# IO.net
KiCad netlist of a schematic drawn in Altium Designer
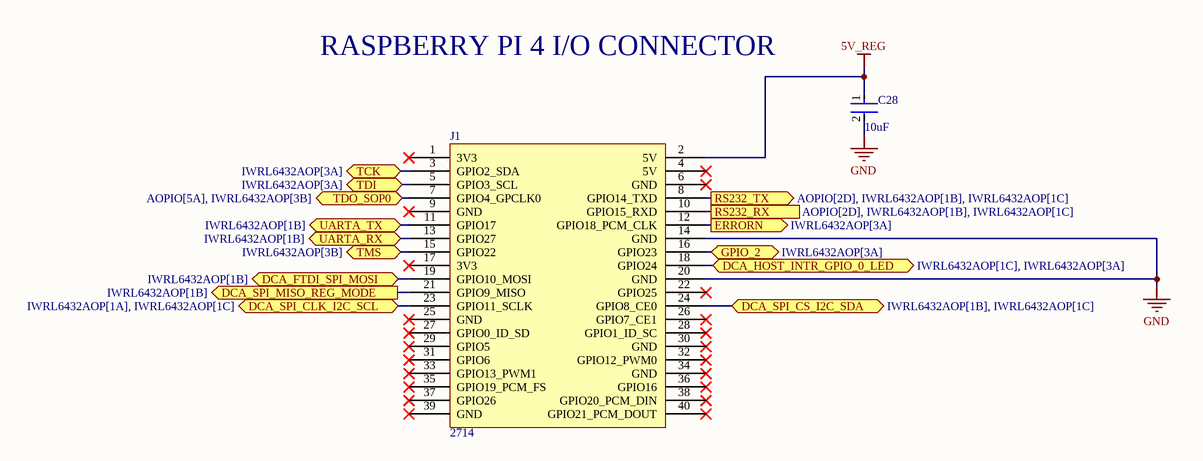
[diagram p0: IO.SchDoc]

(export (version "E")
  (design (tool "Eeschema 10.0.6"))
  (components
    (comp (ref "C28")
      (value "GRM188C81A106MA73D")
      (footprint "FP-GRM188-0_2-MFG")
      (description "Chip Multilayer Ceramic Capacitors for General Purpose, 0603, 10uF, X6S, 22%, 20%, 10V")
      (fields (field (name "TOLERANCE") "20%") (field (name "CAPACITANCE") "10uF"))
      (libsource (lib "Altium Content Vault") (part "11868f565c42a9108669ba33697ecf6"))
    )
    (comp (ref "J1")
      (value "2714")
      (footprint "2714")
      (description "Extra-Tall Smt Gpio Header For Raspberry Pi Hat - 2X20 Extra Tall Female Header ¦Adafruit 2714")
      (fields (field (name "MANUFACTURER") "Adafruit Industries"))
      (libsource (lib "Schlib1") (part "2714"))
    )
  )
  (nets
    (net (code "1") (name "/DCA_FTDI_SPI_MOSI") (class "Default")
      (node (ref "J1") (pin "19") (pinfunction "GPIO10_MOSI_19") (pintype "passive"))
    )
    (net (code "2") (name "/DCA_HOST_INTR_GPIO_0_LED") (class "Default")
      (node (ref "J1") (pin "18") (pinfunction "GPIO24_18") (pintype "passive"))
    )
    (net (code "3") (name "/DCA_SPI_CLK_I2C_SCL") (class "Default")
      (node (ref "J1") (pin "23") (pinfunction "GPIO11_SCLK_23") (pintype "passive"))
    )
    (net (code "4") (name "/DCA_SPI_CS_I2C_SDA") (class "Default")
      (node (ref "J1") (pin "24") (pinfunction "GPIO8_CE0_24") (pintype "passive"))
    )
    (net (code "5") (name "/DCA_SPI_MISO_REG_MODE") (class "Default")
      (node (ref "J1") (pin "21") (pinfunction "GPIO9_MISO_21") (pintype "passive"))
    )
    (net (code "6") (name "/ERRORN") (class "Default")
      (node (ref "J1") (pin "12") (pinfunction "GPIO18_PCM_CLK_12") (pintype "passive"))
    )
    (net (code "7") (name "/GPIO_2") (class "Default")
      (node (ref "J1") (pin "16") (pinfunction "GPIO23_16") (pintype "passive"))
    )
    (net (code "8") (name "/RS232_RX") (class "Default")
      (node (ref "J1") (pin "10") (pinfunction "GPIO15_RXD_10") (pintype "passive"))
    )
    (net (code "9") (name "/RS232_TX") (class "Default")
      (node (ref "J1") (pin "8") (pinfunction "GPIO14_TXD_8") (pintype "passive"))
    )
    (net (code "10") (name "/TCK") (class "Default")
      (node (ref "J1") (pin "3") (pinfunction "GPIO2_SDA_3") (pintype "passive"))
    )
    (net (code "11") (name "/TDI") (class "Default")
      (node (ref "J1") (pin "5") (pinfunction "GPIO3_SCL_5") (pintype "passive"))
    )
    (net (code "12") (name "/TDO_SOP0") (class "Default")
      (node (ref "J1") (pin "7") (pinfunction "GPIO4_GPCLK0_7") (pintype "passive"))
    )
    (net (code "13") (name "/TMS") (class "Default")
      (node (ref "J1") (pin "15") (pinfunction "GPIO22_15") (pintype "passive"))
    )
    (net (code "14") (name "/UARTA_RX") (class "Default")
      (node (ref "J1") (pin "13") (pinfunction "GPIO27_13") (pintype "passive"))
    )
    (net (code "15") (name "/UARTA_TX") (class "Default")
      (node (ref "J1") (pin "11") (pinfunction "GPIO17_11") (pintype "passive"))
    )
    (net (code "16") (name "5V_REG") (class "Default")
      (node (ref "C28") (pin "1") (pinfunction "1_1") (pintype "passive"))
      (node (ref "J1") (pin "2") (pinfunction "5V_2") (pintype "passive"))
    )
    (net (code "17") (name "GND") (class "Default")
      (node (ref "C28") (pin "2") (pinfunction "2_2") (pintype "passive"))
      (node (ref "J1") (pin "14") (pinfunction "GND_14") (pintype "passive"))
      (node (ref "J1") (pin "20") (pinfunction "GND_20") (pintype "passive"))
    )
    (net (code "18") (name "unconnected-(J1-3V3-Pad1)") (class "Default")
      (node (ref "J1") (pin "1") (pinfunction "3V3_1") (pintype "passive+no_connect"))
    )
    (net (code "19") (name "unconnected-(J1-3V3-Pad17)") (class "Default")
      (node (ref "J1") (pin "17") (pinfunction "3V3_17") (pintype "passive+no_connect"))
    )
    (net (code "20") (name "unconnected-(J1-5V-Pad4)") (class "Default")
      (node (ref "J1") (pin "4") (pinfunction "5V_4") (pintype "passive+no_connect"))
    )
    (net (code "21") (name "unconnected-(J1-GND-Pad6)") (class "Default")
      (node (ref "J1") (pin "6") (pinfunction "GND_6") (pintype "passive+no_connect"))
    )
    (net (code "22") (name "unconnected-(J1-GND-Pad9)") (class "Default")
      (node (ref "J1") (pin "9") (pinfunction "GND_9") (pintype "passive+no_connect"))
    )
    (net (code "23") (name "unconnected-(J1-GND-Pad25)") (class "Default")
      (node (ref "J1") (pin "25") (pinfunction "GND_25") (pintype "passive+no_connect"))
    )
    (net (code "24") (name "unconnected-(J1-GND-Pad30)") (class "Default")
      (node (ref "J1") (pin "30") (pinfunction "GND_30") (pintype "passive+no_connect"))
    )
    (net (code "25") (name "unconnected-(J1-GND-Pad34)") (class "Default")
      (node (ref "J1") (pin "34") (pinfunction "GND_34") (pintype "passive+no_connect"))
    )
    (net (code "26") (name "unconnected-(J1-GND-Pad39)") (class "Default")
      (node (ref "J1") (pin "39") (pinfunction "GND_39") (pintype "passive+no_connect"))
    )
    (net (code "27") (name "unconnected-(J1-GPIO0_ID_SD-Pad27)") (class "Default")
      (node (ref "J1") (pin "27") (pinfunction "GPIO0_ID_SD_27") (pintype "passive+no_connect"))
    )
    (net (code "28") (name "unconnected-(J1-GPIO1_ID_SC-Pad28)") (class "Default")
      (node (ref "J1") (pin "28") (pinfunction "GPIO1_ID_SC_28") (pintype "passive+no_connect"))
    )
    (net (code "29") (name "unconnected-(J1-GPIO5-Pad29)") (class "Default")
      (node (ref "J1") (pin "29") (pinfunction "GPIO5_29") (pintype "passive+no_connect"))
    )
    (net (code "30") (name "unconnected-(J1-GPIO6-Pad31)") (class "Default")
      (node (ref "J1") (pin "31") (pinfunction "GPIO6_31") (pintype "passive+no_connect"))
    )
    (net (code "31") (name "unconnected-(J1-GPIO7_CE1-Pad26)") (class "Default")
      (node (ref "J1") (pin "26") (pinfunction "GPIO7_CE1_26") (pintype "passive+no_connect"))
    )
    (net (code "32") (name "unconnected-(J1-GPIO12_PWM0-Pad32)") (class "Default")
      (node (ref "J1") (pin "32") (pinfunction "GPIO12_PWM0_32") (pintype "passive+no_connect"))
    )
    (net (code "33") (name "unconnected-(J1-GPIO13_PWM1-Pad33)") (class "Default")
      (node (ref "J1") (pin "33") (pinfunction "GPIO13_PWM1_33") (pintype "passive+no_connect"))
    )
    (net (code "34") (name "unconnected-(J1-GPIO16-Pad36)") (class "Default")
      (node (ref "J1") (pin "36") (pinfunction "GPIO16_36") (pintype "passive+no_connect"))
    )
    (net (code "35") (name "unconnected-(J1-GPIO19_PCM_FS-Pad35)") (class "Default")
      (node (ref "J1") (pin "35") (pinfunction "GPIO19_PCM_FS_35") (pintype "passive+no_connect"))
    )
    (net (code "36") (name "unconnected-(J1-GPIO20_PCM_DIN-Pad38)") (class "Default")
      (node (ref "J1") (pin "38") (pinfunction "GPIO20_PCM_DIN_38") (pintype "passive+no_connect"))
    )
    (net (code "37") (name "unconnected-(J1-GPIO21_PCM_DOUT-Pad40)") (class "Default")
      (node (ref "J1") (pin "40") (pinfunction "GPIO21_PCM_DOUT_40") (pintype "passive+no_connect"))
    )
    (net (code "38") (name "unconnected-(J1-GPIO25-Pad22)") (class "Default")
      (node (ref "J1") (pin "22") (pinfunction "GPIO25_22") (pintype "passive+no_connect"))
    )
    (net (code "39") (name "unconnected-(J1-GPIO26-Pad37)") (class "Default")
      (node (ref "J1") (pin "37") (pinfunction "GPIO26_37") (pintype "passive+no_connect"))
    )
  )
)
